# debug.net
KiCad netlist of a schematic drawn in Altium Designer
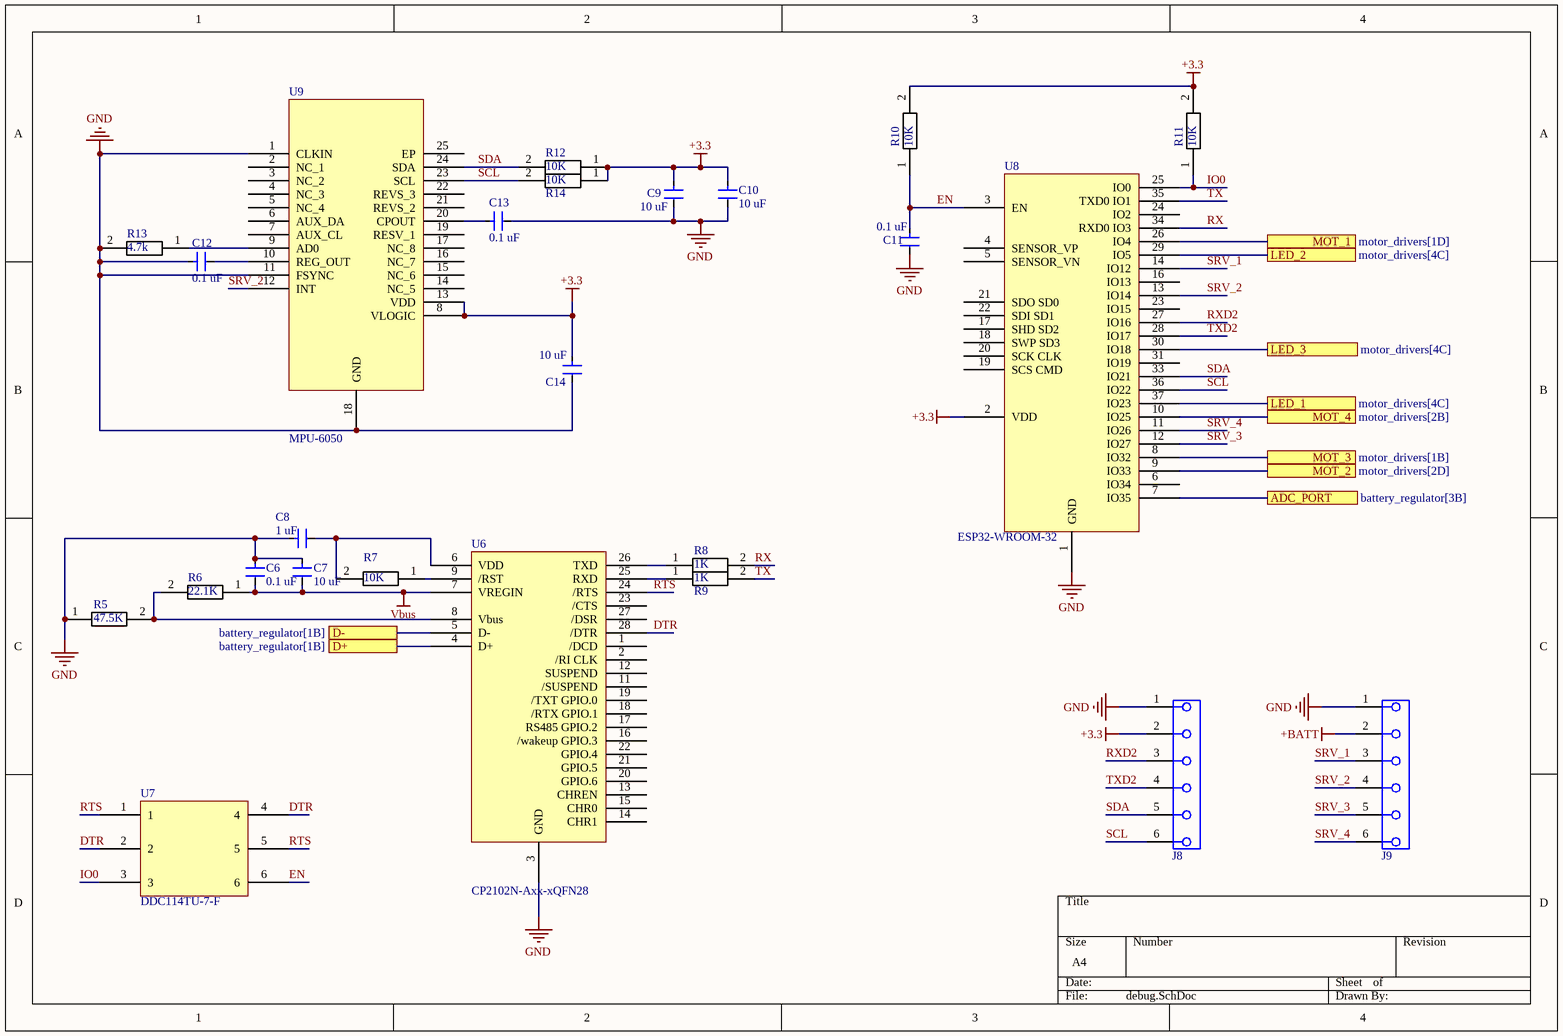
[diagram p0: debug.SchDoc]

(export (version "E")
  (design (tool "Eeschema 10.0.6"))
  (components
    (comp (ref "C6")
      (value "0.1 uF")
      (footprint "res0805ph")
      (fields (field (name "TOLERANCE") "20%"))
      (libsource (lib "LibraryTechnologie") (part "CER Capacitor_1"))
    )
    (comp (ref "C7")
      (value "10 uF")
      (footprint "res0805ph")
      (fields (field (name "TOLERANCE") "20%"))
      (libsource (lib "LibraryTechnologie") (part "CER Capacitor_1"))
    )
    (comp (ref "C8")
      (value "1 uF")
      (footprint "res0805ph")
      (fields (field (name "TOLERANCE") "20%"))
      (libsource (lib "LibraryTechnologie") (part "CER Capacitor_1"))
    )
    (comp (ref "C9")
      (value "10 uF")
      (footprint "res0805ph")
      (fields (field (name "TOLERANCE") "20%"))
      (libsource (lib "LibraryTechnologie") (part "CER Capacitor_1"))
    )
    (comp (ref "C10")
      (value "10 uF")
      (footprint "res0805ph")
      (fields (field (name "TOLERANCE") "20%"))
      (libsource (lib "LibraryTechnologie") (part "CER Capacitor_1"))
    )
    (comp (ref "C11")
      (value "0.1 uF")
      (footprint "res0805ph")
      (fields (field (name "TOLERANCE") "20%"))
      (libsource (lib "LibraryTechnologie") (part "CER Capacitor_1"))
    )
    (comp (ref "C12")
      (value "0.1 uF")
      (footprint "res0805ph")
      (fields (field (name "TOLERANCE") "20%"))
      (libsource (lib "LibraryTechnologie") (part "CER Capacitor_1"))
    )
    (comp (ref "C13")
      (value "0.1 uF")
      (footprint "res0805ph")
      (fields (field (name "TOLERANCE") "20%"))
      (libsource (lib "LibraryTechnologie") (part "CER Capacitor_1"))
    )
    (comp (ref "C14")
      (value "10 uF")
      (footprint "res0805ph")
      (fields (field (name "TOLERANCE") "20%"))
      (libsource (lib "LibraryTechnologie") (part "CER Capacitor_1"))
    )
    (comp (ref "J8")
      (value "SSW-106-02-T-S-RA")
      (footprint "61300611121")
      (description "SQ Post Socket, Through-hole, Right Angle, -55 to 105 degC, 2.54mm Pitch, 6-Pin, Female, RoHS")
      (fields (field (name "MANUFACTURER") "Samtec"))
      (libsource (lib "LibraryTechnologie (1)") (part "Connector 1x6_1"))
    )
    (comp (ref "J9")
      (value "SSW-106-02-T-S-RA")
      (footprint "61300611121")
      (description "SQ Post Socket, Through-hole, Right Angle, -55 to 105 degC, 2.54mm Pitch, 6-Pin, Female, RoHS")
      (fields (field (name "MANUFACTURER") "Samtec"))
      (libsource (lib "LibraryTechnologie (1)") (part "Connector 1x6_1"))
    )
    (comp (ref "R5")
      (value "47.5K")
      (footprint "res0805ph")
      (description "RES SMD 5.9K OHM 1% 1/4W 1206")
      (fields
        (field (name "OCTOPART") "https://octopart.com/ac1206fr-075k9l-yageo-30511161")
        (field (name "MANUFACTURER") "Yageo")
      )
      (libsource (lib "LibraryTechnologie") (part "Weerstand"))
    )
    (comp (ref "R6")
      (value "22.1K")
      (footprint "res0805ph")
      (description "RES SMD 5.9K OHM 1% 1/4W 1206")
      (fields
        (field (name "OCTOPART") "https://octopart.com/ac1206fr-075k9l-yageo-30511161")
        (field (name "MANUFACTURER") "Yageo")
      )
      (libsource (lib "LibraryTechnologie") (part "Weerstand"))
    )
    (comp (ref "R7")
      (value "10K")
      (footprint "res0805ph")
      (description "RES SMD 5.9K OHM 1% 1/4W 1206")
      (fields
        (field (name "OCTOPART") "https://octopart.com/ac1206fr-075k9l-yageo-30511161")
        (field (name "MANUFACTURER") "Yageo")
      )
      (libsource (lib "LibraryTechnologie") (part "Weerstand"))
    )
    (comp (ref "R8")
      (value "1K")
      (footprint "res0805ph")
      (description "RES SMD 5.9K OHM 1% 1/4W 1206")
      (fields
        (field (name "OCTOPART") "https://octopart.com/ac1206fr-075k9l-yageo-30511161")
        (field (name "MANUFACTURER") "Yageo")
      )
      (libsource (lib "LibraryTechnologie") (part "Weerstand"))
    )
    (comp (ref "R9")
      (value "1K")
      (footprint "res0805ph")
      (description "RES SMD 5.9K OHM 1% 1/4W 1206")
      (fields
        (field (name "OCTOPART") "https://octopart.com/ac1206fr-075k9l-yageo-30511161")
        (field (name "MANUFACTURER") "Yageo")
      )
      (libsource (lib "LibraryTechnologie") (part "Weerstand"))
    )
    (comp (ref "R10")
      (value "10K")
      (footprint "res0805ph")
      (description "RES SMD 5.9K OHM 1% 1/4W 1206")
      (fields
        (field (name "OCTOPART") "https://octopart.com/ac1206fr-075k9l-yageo-30511161")
        (field (name "MANUFACTURER") "Yageo")
      )
      (libsource (lib "LibraryTechnologie") (part "Weerstand"))
    )
    (comp (ref "R11")
      (value "10K")
      (footprint "res0805ph")
      (description "RES SMD 5.9K OHM 1% 1/4W 1206")
      (fields
        (field (name "OCTOPART") "https://octopart.com/ac1206fr-075k9l-yageo-30511161")
        (field (name "MANUFACTURER") "Yageo")
      )
      (libsource (lib "LibraryTechnologie") (part "Weerstand"))
    )
    (comp (ref "R12")
      (value "10K")
      (footprint "res0805ph")
      (description "RES SMD 5.9K OHM 1% 1/4W 1206")
      (fields
        (field (name "OCTOPART") "https://octopart.com/ac1206fr-075k9l-yageo-30511161")
        (field (name "MANUFACTURER") "Yageo")
      )
      (libsource (lib "LibraryTechnologie") (part "Weerstand"))
    )
    (comp (ref "R13")
      (value "4.7k")
      (footprint "res0805ph")
      (description "RES SMD 5.9K OHM 1% 1/4W 1206")
      (fields
        (field (name "OCTOPART") "https://octopart.com/ac1206fr-075k9l-yageo-30511161")
        (field (name "MANUFACTURER") "Yageo")
      )
      (libsource (lib "LibraryTechnologie") (part "Weerstand"))
    )
    (comp (ref "R14")
      (value "10K")
      (footprint "res0805ph")
      (description "RES SMD 5.9K OHM 1% 1/4W 1206")
      (fields
        (field (name "OCTOPART") "https://octopart.com/ac1206fr-075k9l-yageo-30511161")
        (field (name "MANUFACTURER") "Yageo")
      )
      (libsource (lib "LibraryTechnologie") (part "Weerstand"))
    )
    (comp (ref "U6")
      (value "CP2102N-Axx-xQFN28")
      (footprint "QFN50P500X500X80-29N")
      (libsource (lib "Dronesch") (part "CP2102N-Axx-xQFN28"))
    )
    (comp (ref "U7")
      (value "DDC114TU-7-F")
      (footprint "SOT65P210X110-6N")
      (libsource (lib "Dronesch") (part "DDC114TU-7-F"))
    )
    (comp (ref "U8")
      (value "ESP32-WROOM-32")
      (footprint "ESP32-WROOM-32D")
      (libsource (lib "Dronesch") (part "ESP32-WROOM-32"))
    )
    (comp (ref "U9")
      (value "MPU-6050")
      (footprint "IS-QFN-24_V")
      (libsource (lib "Dronesch") (part "MPU-6050"))
    )
  )
  (nets
    (net (code "1") (name "+3.3") (class "Default")
      (node (ref "C10") (pin "1") (pinfunction "1_1") (pintype "passive"))
      (node (ref "C14") (pin "1") (pinfunction "1_1") (pintype "passive"))
      (node (ref "C9") (pin "1") (pinfunction "1_1") (pintype "passive"))
      (node (ref "J8") (pin "2") (pinfunction "2_2") (pintype "passive"))
      (node (ref "R10") (pin "2") (pinfunction "2_2") (pintype "passive"))
      (node (ref "R11") (pin "2") (pinfunction "2_2") (pintype "passive"))
      (node (ref "R12") (pin "1") (pinfunction "1_1") (pintype "passive"))
      (node (ref "R14") (pin "1") (pinfunction "1_1") (pintype "passive"))
      (node (ref "U8") (pin "2") (pinfunction "VDD_2") (pintype "passive"))
      (node (ref "U9") (pin "13") (pinfunction "VDD_13") (pintype "passive"))
      (node (ref "U9") (pin "8") (pinfunction "VLOGIC_8") (pintype "passive"))
    )
    (net (code "2") (name "+BATT") (class "Default")
      (node (ref "J9") (pin "2") (pinfunction "2_2") (pintype "passive"))
    )
    (net (code "3") (name "/ADC_PORT") (class "Default")
      (node (ref "U8") (pin "7") (pinfunction "IO35_7") (pintype "passive"))
    )
    (net (code "4") (name "/D+") (class "Default")
      (node (ref "U6") (pin "4") (pinfunction "D+_4") (pintype "passive"))
    )
    (net (code "5") (name "/D-") (class "Default")
      (node (ref "U6") (pin "5") (pinfunction "D-_5") (pintype "passive"))
    )
    (net (code "6") (name "/DTR") (class "Default")
      (node (ref "U6") (pin "28") (pinfunction "/DTR_28") (pintype "passive"))
      (node (ref "U7") (pin "2") (pinfunction "2_2") (pintype "passive"))
      (node (ref "U7") (pin "4") (pinfunction "4_4") (pintype "passive"))
    )
    (net (code "7") (name "/EN") (class "Default")
      (node (ref "C11") (pin "1") (pinfunction "1_1") (pintype "passive"))
      (node (ref "R10") (pin "1") (pinfunction "1_1") (pintype "passive"))
      (node (ref "U7") (pin "6") (pinfunction "6_6") (pintype "passive"))
      (node (ref "U8") (pin "3") (pinfunction "EN_3") (pintype "passive"))
    )
    (net (code "8") (name "/IO0") (class "Default")
      (node (ref "R11") (pin "1") (pinfunction "1_1") (pintype "passive"))
      (node (ref "U7") (pin "3") (pinfunction "3_3") (pintype "passive"))
      (node (ref "U8") (pin "25") (pinfunction "IO0_25") (pintype "passive"))
    )
    (net (code "9") (name "/LED_1") (class "Default")
      (node (ref "U8") (pin "37") (pinfunction "IO23_37") (pintype "passive"))
    )
    (net (code "10") (name "/LED_2") (class "Default")
      (node (ref "U8") (pin "29") (pinfunction "IO5_29") (pintype "passive"))
    )
    (net (code "11") (name "/LED_3") (class "Default")
      (node (ref "U8") (pin "30") (pinfunction "IO18_30") (pintype "passive"))
    )
    (net (code "12") (name "/MOT_1") (class "Default")
      (node (ref "U8") (pin "26") (pinfunction "IO4_26") (pintype "passive"))
    )
    (net (code "13") (name "/MOT_2") (class "Default")
      (node (ref "U8") (pin "9") (pinfunction "IO33_9") (pintype "passive"))
    )
    (net (code "14") (name "/MOT_3") (class "Default")
      (node (ref "U8") (pin "8") (pinfunction "IO32_8") (pintype "passive"))
    )
    (net (code "15") (name "/MOT_4") (class "Default")
      (node (ref "U8") (pin "10") (pinfunction "IO25_10") (pintype "passive"))
    )
    (net (code "16") (name "/RTS") (class "Default")
      (node (ref "U6") (pin "24") (pinfunction "/RTS_24") (pintype "passive"))
      (node (ref "U7") (pin "1") (pinfunction "1_1") (pintype "passive"))
      (node (ref "U7") (pin "5") (pinfunction "5_5") (pintype "passive"))
    )
    (net (code "17") (name "/RX") (class "Default")
      (node (ref "R8") (pin "2") (pinfunction "2_2") (pintype "passive"))
      (node (ref "U8") (pin "34") (pinfunction "RXD0_IO3_34") (pintype "passive"))
    )
    (net (code "18") (name "/RXD2") (class "Default")
      (node (ref "J8") (pin "3") (pinfunction "3_3") (pintype "passive"))
      (node (ref "U8") (pin "27") (pinfunction "IO16_27") (pintype "passive"))
    )
    (net (code "19") (name "/SCL") (class "Default")
      (node (ref "J8") (pin "6") (pinfunction "6_6") (pintype "passive"))
      (node (ref "R14") (pin "2") (pinfunction "2_2") (pintype "passive"))
      (node (ref "U8") (pin "36") (pinfunction "IO22_36") (pintype "passive"))
      (node (ref "U9") (pin "23") (pinfunction "SCL_23") (pintype "passive"))
    )
    (net (code "20") (name "/SDA") (class "Default")
      (node (ref "J8") (pin "5") (pinfunction "5_5") (pintype "passive"))
      (node (ref "R12") (pin "2") (pinfunction "2_2") (pintype "passive"))
      (node (ref "U8") (pin "33") (pinfunction "IO21_33") (pintype "passive"))
      (node (ref "U9") (pin "24") (pinfunction "SDA_24") (pintype "passive"))
    )
    (net (code "21") (name "/SRV_1") (class "Default")
      (node (ref "J9") (pin "3") (pinfunction "3_3") (pintype "passive"))
      (node (ref "U8") (pin "14") (pinfunction "IO12_14") (pintype "passive"))
    )
    (net (code "22") (name "/SRV_2") (class "Default")
      (node (ref "J9") (pin "4") (pinfunction "4_4") (pintype "passive"))
      (node (ref "U8") (pin "13") (pinfunction "IO14_13") (pintype "passive"))
      (node (ref "U9") (pin "12") (pinfunction "INT_12") (pintype "passive"))
    )
    (net (code "23") (name "/SRV_3") (class "Default")
      (node (ref "J9") (pin "5") (pinfunction "5_5") (pintype "passive"))
      (node (ref "U8") (pin "12") (pinfunction "IO27_12") (pintype "passive"))
    )
    (net (code "24") (name "/SRV_4") (class "Default")
      (node (ref "J9") (pin "6") (pinfunction "6_6") (pintype "passive"))
      (node (ref "U8") (pin "11") (pinfunction "IO26_11") (pintype "passive"))
    )
    (net (code "25") (name "/TX") (class "Default")
      (node (ref "R9") (pin "2") (pinfunction "2_2") (pintype "passive"))
      (node (ref "U8") (pin "35") (pinfunction "TXD0_IO1_35") (pintype "passive"))
    )
    (net (code "26") (name "/TXD2") (class "Default")
      (node (ref "J8") (pin "4") (pinfunction "4_4") (pintype "passive"))
      (node (ref "U8") (pin "28") (pinfunction "IO17_28") (pintype "passive"))
    )
    (net (code "27") (name "GND") (class "Default")
      (node (ref "C10") (pin "2") (pinfunction "2_2") (pintype "passive"))
      (node (ref "C11") (pin "2") (pinfunction "2_2") (pintype "passive"))
      (node (ref "C12") (pin "1") (pinfunction "1_1") (pintype "passive"))
      (node (ref "C13") (pin "2") (pinfunction "2_2") (pintype "passive"))
      (node (ref "C14") (pin "2") (pinfunction "2_2") (pintype "passive"))
      (node (ref "C6") (pin "1") (pinfunction "1_1") (pintype "passive"))
      (node (ref "C7") (pin "1") (pinfunction "1_1") (pintype "passive"))
      (node (ref "C8") (pin "1") (pinfunction "1_1") (pintype "passive"))
      (node (ref "C9") (pin "2") (pinfunction "2_2") (pintype "passive"))
      (node (ref "J8") (pin "1") (pinfunction "1_1") (pintype "passive"))
      (node (ref "J9") (pin "1") (pinfunction "1_1") (pintype "passive"))
      (node (ref "R13") (pin "2") (pinfunction "2_2") (pintype "passive"))
      (node (ref "R5") (pin "1") (pinfunction "1_1") (pintype "passive"))
      (node (ref "U6") (pin "3") (pinfunction "GND_3") (pintype "passive"))
      (node (ref "U8") (pin "1") (pinfunction "GND_1") (pintype "passive"))
      (node (ref "U9") (pin "1") (pinfunction "CLKIN_1") (pintype "passive"))
      (node (ref "U9") (pin "11") (pinfunction "FSYNC_11") (pintype "passive"))
      (node (ref "U9") (pin "18") (pinfunction "GND_18") (pintype "passive"))
    )
    (net (code "28") (name "Net-(U6-RXD)") (class "Default")
      (node (ref "R9") (pin "1") (pinfunction "1_1") (pintype "passive"))
      (node (ref "U6") (pin "25") (pinfunction "RXD_25") (pintype "passive"))
    )
    (net (code "29") (name "Net-(U6-TXD)") (class "Default")
      (node (ref "R8") (pin "1") (pinfunction "1_1") (pintype "passive"))
      (node (ref "U6") (pin "26") (pinfunction "TXD_26") (pintype "passive"))
    )
    (net (code "30") (name "Net-(U6-VDD)") (class "Default")
      (node (ref "C8") (pin "2") (pinfunction "2_2") (pintype "passive"))
      (node (ref "R7") (pin "2") (pinfunction "2_2") (pintype "passive"))
      (node (ref "U6") (pin "6") (pinfunction "VDD_6") (pintype "passive"))
    )
    (net (code "31") (name "Net-(U6-Vbus)") (class "Default")
      (node (ref "R5") (pin "2") (pinfunction "2_2") (pintype "passive"))
      (node (ref "R6") (pin "2") (pinfunction "2_2") (pintype "passive"))
      (node (ref "U6") (pin "8") (pinfunction "Vbus_8") (pintype "passive"))
    )
    (net (code "32") (name "Net-(U6-{slash}RST)") (class "Default")
      (node (ref "R7") (pin "1") (pinfunction "1_1") (pintype "passive"))
      (node (ref "U6") (pin "9") (pinfunction "/RST_9") (pintype "passive"))
    )
    (net (code "33") (name "Net-(U9-AD0)") (class "Default")
      (node (ref "R13") (pin "1") (pinfunction "1_1") (pintype "passive"))
      (node (ref "U9") (pin "9") (pinfunction "AD0_9") (pintype "passive"))
    )
    (net (code "34") (name "Net-(U9-CPOUT)") (class "Default")
      (node (ref "C13") (pin "1") (pinfunction "1_1") (pintype "passive"))
      (node (ref "U9") (pin "20") (pinfunction "CPOUT_20") (pintype "passive"))
    )
    (net (code "35") (name "Net-(U9-REG_OUT)") (class "Default")
      (node (ref "C12") (pin "2") (pinfunction "2_2") (pintype "passive"))
      (node (ref "U9") (pin "10") (pinfunction "REG_OUT_10") (pintype "passive"))
    )
    (net (code "36") (name "Vbus") (class "Default")
      (node (ref "C6") (pin "2") (pinfunction "2_2") (pintype "passive"))
      (node (ref "C7") (pin "2") (pinfunction "2_2") (pintype "passive"))
      (node (ref "R6") (pin "1") (pinfunction "1_1") (pintype "passive"))
      (node (ref "U6") (pin "7") (pinfunction "VREGIN_7") (pintype "passive"))
    )
    (net (code "37") (name "unconnected-(U6-CHR0-Pad15)") (class "Default")
      (node (ref "U6") (pin "15") (pinfunction "CHR0_15") (pintype "passive"))
    )
    (net (code "38") (name "unconnected-(U6-CHR1-Pad14)") (class "Default")
      (node (ref "U6") (pin "14") (pinfunction "CHR1_14") (pintype "passive"))
    )
    (net (code "39") (name "unconnected-(U6-CHREN-Pad13)") (class "Default")
      (node (ref "U6") (pin "13") (pinfunction "CHREN_13") (pintype "passive"))
    )
    (net (code "40") (name "unconnected-(U6-GPIO.4-Pad22)") (class "Default")
      (node (ref "U6") (pin "22") (pinfunction "GPIO.4_22") (pintype "passive"))
    )
    (net (code "41") (name "unconnected-(U6-GPIO.5-Pad21)") (class "Default")
      (node (ref "U6") (pin "21") (pinfunction "GPIO.5_21") (pintype "passive"))
    )
    (net (code "42") (name "unconnected-(U6-GPIO.6-Pad20)") (class "Default")
      (node (ref "U6") (pin "20") (pinfunction "GPIO.6_20") (pintype "passive"))
    )
    (net (code "43") (name "unconnected-(U6-RS485_GPIO.2-Pad17)") (class "Default")
      (node (ref "U6") (pin "17") (pinfunction "RS485_GPIO.2_17") (pintype "passive"))
    )
    (net (code "44") (name "unconnected-(U6-SUSPEND-Pad12)") (class "Default")
      (node (ref "U6") (pin "12") (pinfunction "SUSPEND_12") (pintype "passive"))
    )
    (net (code "45") (name "unconnected-(U6-{slash}CTS-Pad23)") (class "Default")
      (node (ref "U6") (pin "23") (pinfunction "/CTS_23") (pintype "passive"))
    )
    (net (code "46") (name "unconnected-(U6-{slash}DCD-Pad1)") (class "Default")
      (node (ref "U6") (pin "1") (pinfunction "/DCD_1") (pintype "passive"))
    )
    (net (code "47") (name "unconnected-(U6-{slash}DSR-Pad27)") (class "Default")
      (node (ref "U6") (pin "27") (pinfunction "/DSR_27") (pintype "passive"))
    )
    (net (code "48") (name "unconnected-(U6-{slash}RI_CLK-Pad2)") (class "Default")
      (node (ref "U6") (pin "2") (pinfunction "/RI_CLK_2") (pintype "passive"))
    )
    (net (code "49") (name "unconnected-(U6-{slash}RTX_GPIO.1-Pad18)") (class "Default")
      (node (ref "U6") (pin "18") (pinfunction "/RTX_GPIO.1_18") (pintype "passive"))
    )
    (net (code "50") (name "unconnected-(U6-{slash}SUSPEND-Pad11)") (class "Default")
      (node (ref "U6") (pin "11") (pinfunction "/SUSPEND_11") (pintype "passive"))
    )
    (net (code "51") (name "unconnected-(U6-{slash}TXT_GPIO.0-Pad19)") (class "Default")
      (node (ref "U6") (pin "19") (pinfunction "/TXT_GPIO.0_19") (pintype "passive"))
    )
    (net (code "52") (name "unconnected-(U6-{slash}wakeup_GPIO.3-Pad16)") (class "Default")
      (node (ref "U6") (pin "16") (pinfunction "/wakeup_GPIO.3_16") (pintype "passive"))
    )
    (net (code "53") (name "unconnected-(U8-IO2-Pad24)") (class "Default")
      (node (ref "U8") (pin "24") (pinfunction "IO2_24") (pintype "passive"))
    )
    (net (code "54") (name "unconnected-(U8-IO13-Pad16)") (class "Default")
      (node (ref "U8") (pin "16") (pinfunction "IO13_16") (pintype "passive"))
    )
    (net (code "55") (name "unconnected-(U8-IO15-Pad23)") (class "Default")
      (node (ref "U8") (pin "23") (pinfunction "IO15_23") (pintype "passive"))
    )
    (net (code "56") (name "unconnected-(U8-IO19-Pad31)") (class "Default")
      (node (ref "U8") (pin "31") (pinfunction "IO19_31") (pintype "passive"))
    )
    (net (code "57") (name "unconnected-(U8-IO34-Pad6)") (class "Default")
      (node (ref "U8") (pin "6") (pinfunction "IO34_6") (pintype "passive"))
    )
    (net (code "58") (name "unconnected-(U8-SCK_CLK-Pad20)") (class "Default")
      (node (ref "U8") (pin "20") (pinfunction "SCK_CLK_20") (pintype "passive"))
    )
    (net (code "59") (name "unconnected-(U8-SCS_CMD-Pad19)") (class "Default")
      (node (ref "U8") (pin "19") (pinfunction "SCS_CMD_19") (pintype "passive"))
    )
    (net (code "60") (name "unconnected-(U8-SDI_SD1-Pad22)") (class "Default")
      (node (ref "U8") (pin "22") (pinfunction "SDI_SD1_22") (pintype "passive"))
    )
    (net (code "61") (name "unconnected-(U8-SDO_SD0-Pad21)") (class "Default")
      (node (ref "U8") (pin "21") (pinfunction "SDO_SD0_21") (pintype "passive"))
    )
    (net (code "62") (name "unconnected-(U8-SENSOR_VN-Pad5)") (class "Default")
      (node (ref "U8") (pin "5") (pinfunction "SENSOR_VN_5") (pintype "passive"))
    )
    (net (code "63") (name "unconnected-(U8-SENSOR_VP-Pad4)") (class "Default")
      (node (ref "U8") (pin "4") (pinfunction "SENSOR_VP_4") (pintype "passive"))
    )
    (net (code "64") (name "unconnected-(U8-SHD_SD2-Pad17)") (class "Default")
      (node (ref "U8") (pin "17") (pinfunction "SHD_SD2_17") (pintype "passive"))
    )
    (net (code "65") (name "unconnected-(U8-SWP_SD3-Pad18)") (class "Default")
      (node (ref "U8") (pin "18") (pinfunction "SWP_SD3_18") (pintype "passive"))
    )
    (net (code "66") (name "unconnected-(U9-AUX_CL-Pad7)") (class "Default")
      (node (ref "U9") (pin "7") (pinfunction "AUX_CL_7") (pintype "passive"))
    )
    (net (code "67") (name "unconnected-(U9-AUX_DA-Pad6)") (class "Default")
      (node (ref "U9") (pin "6") (pinfunction "AUX_DA_6") (pintype "passive"))
    )
    (net (code "68") (name "unconnected-(U9-EP-Pad25)") (class "Default")
      (node (ref "U9") (pin "25") (pinfunction "EP_25") (pintype "passive"))
    )
    (net (code "69") (name "unconnected-(U9-NC_1-Pad2)") (class "Default")
      (node (ref "U9") (pin "2") (pinfunction "NC_1_2") (pintype "passive"))
    )
    (net (code "70") (name "unconnected-(U9-NC_2-Pad3)") (class "Default")
      (node (ref "U9") (pin "3") (pinfunction "NC_2_3") (pintype "passive"))
    )
    (net (code "71") (name "unconnected-(U9-NC_3-Pad4)") (class "Default")
      (node (ref "U9") (pin "4") (pinfunction "NC_3_4") (pintype "passive"))
    )
    (net (code "72") (name "unconnected-(U9-NC_4-Pad5)") (class "Default")
      (node (ref "U9") (pin "5") (pinfunction "NC_4_5") (pintype "passive"))
    )
    (net (code "73") (name "unconnected-(U9-NC_5-Pad14)") (class "Default")
      (node (ref "U9") (pin "14") (pinfunction "NC_5_14") (pintype "passive"))
    )
    (net (code "74") (name "unconnected-(U9-NC_6-Pad15)") (class "Default")
      (node (ref "U9") (pin "15") (pinfunction "NC_6_15") (pintype "passive"))
    )
    (net (code "75") (name "unconnected-(U9-NC_7-Pad16)") (class "Default")
      (node (ref "U9") (pin "16") (pinfunction "NC_7_16") (pintype "passive"))
    )
    (net (code "76") (name "unconnected-(U9-NC_8-Pad17)") (class "Default")
      (node (ref "U9") (pin "17") (pinfunction "NC_8_17") (pintype "passive"))
    )
    (net (code "77") (name "unconnected-(U9-RESV_1-Pad19)") (class "Default")
      (node (ref "U9") (pin "19") (pinfunction "RESV_1_19") (pintype "passive"))
    )
    (net (code "78") (name "unconnected-(U9-REVS_2-Pad21)") (class "Default")
      (node (ref "U9") (pin "21") (pinfunction "REVS_2_21") (pintype "passive"))
    )
    (net (code "79") (name "unconnected-(U9-REVS_3-Pad22)") (class "Default")
      (node (ref "U9") (pin "22") (pinfunction "REVS_3_22") (pintype "passive"))
    )
  )
)
